# am.net
KiCad netlist of a schematic drawn in Altium Designer
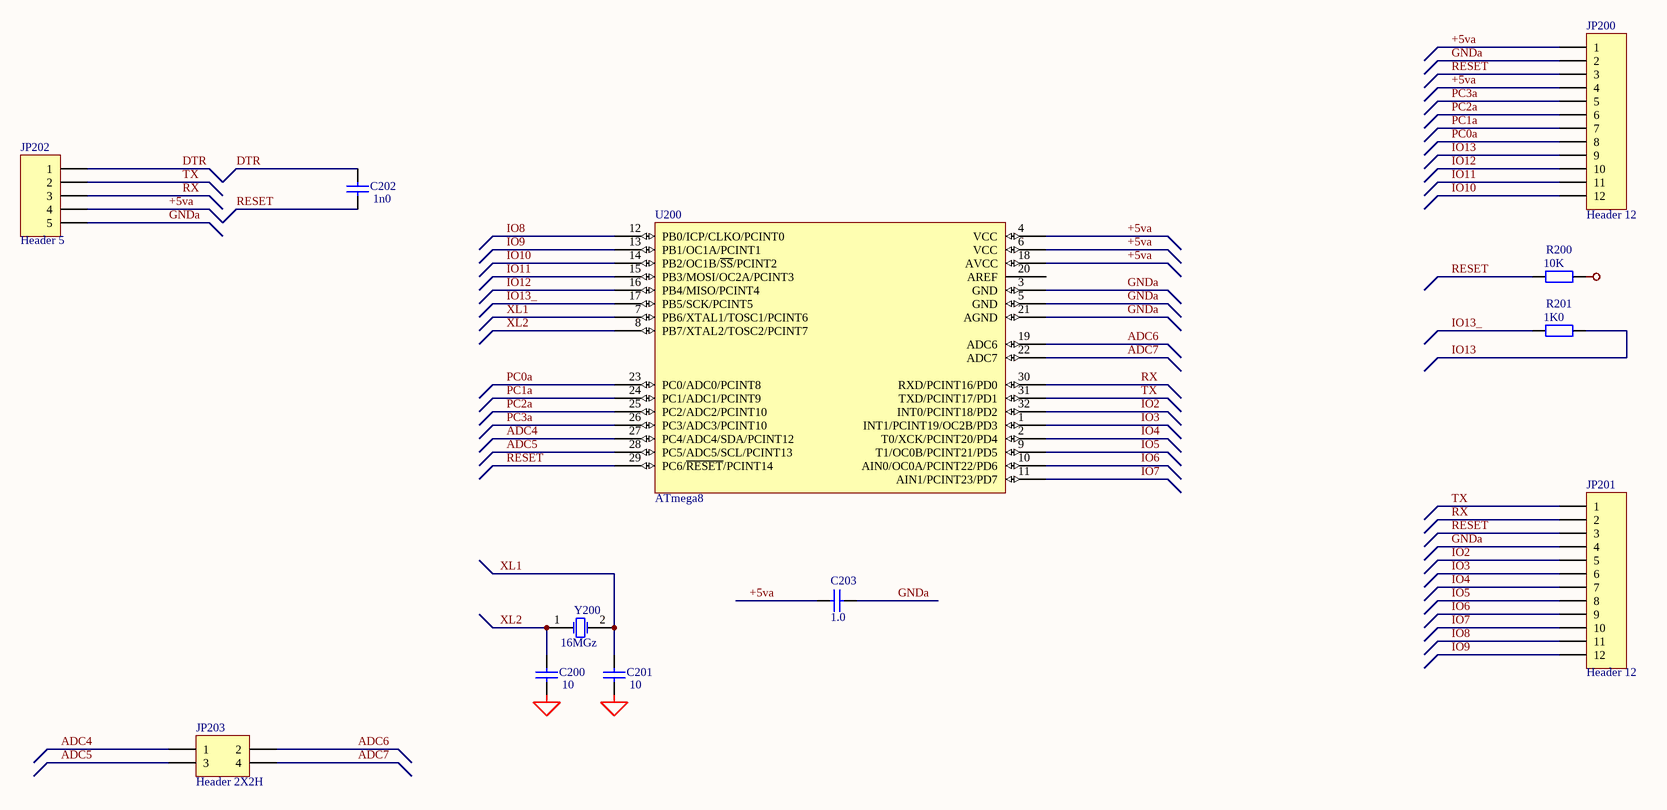
[diagram p0: am.SCHDOC]

(export (version "E")
  (design (tool "Eeschema 10.0.6"))
  (components
    (comp (ref "C200")
      (value "10")
      (footprint "_1206")
      (description "Capacitor")
      (fields (field (name "MANUFACTURER") "Generic Components") (field (name "PUBLISHER") "Altium Limited"))
      (libsource (lib "Miscellaneous Devices") (part "Cap Semi"))
    )
    (comp (ref "C201")
      (value "10")
      (footprint "_1206")
      (description "Capacitor")
      (fields (field (name "MANUFACTURER") "Generic Components") (field (name "PUBLISHER") "Altium Limited"))
      (libsource (lib "Miscellaneous Devices") (part "Cap Semi"))
    )
    (comp (ref "C202")
      (value "1n0")
      (footprint "_1206")
      (description "Capacitor")
      (fields (field (name "MANUFACTURER") "Generic Components") (field (name "PUBLISHER") "Altium Limited"))
      (libsource (lib "Miscellaneous Devices") (part "Cap Semi"))
    )
    (comp (ref "C203")
      (value "1.0")
      (footprint "_1206")
      (description "Capacitor")
      (fields (field (name "MANUFACTURER") "Generic Components") (field (name "PUBLISHER") "Altium Limited"))
      (libsource (lib "Miscellaneous Devices") (part "Cap Semi"))
    )
    (comp (ref "JP200")
      (value "Header 12")
      (footprint "HDR1X12")
      (description "Header, 12-Pin")
      (fields (field (name "MANUFACTURER") "Generic Components") (field (name "PUBLISHER") "Altium Limited"))
      (libsource (lib "Miscellaneous Connectors") (part "Header 12"))
    )
    (comp (ref "JP201")
      (value "Header 12")
      (footprint "HDR1X12")
      (description "Header, 12-Pin")
      (fields (field (name "MANUFACTURER") "Generic Components") (field (name "PUBLISHER") "Altium Limited"))
      (libsource (lib "Miscellaneous Connectors") (part "Header 12"))
    )
    (comp (ref "JP202")
      (value "Header 5")
      (footprint "HDR1X5")
      (description "Header, 5-Pin")
      (fields (field (name "MANUFACTURER") "Generic Components") (field (name "PUBLISHER") "Altium Limited"))
      (libsource (lib "Miscellaneous Connectors") (part "Header 5"))
    )
    (comp (ref "JP203")
      (value "Header 2X2H")
      (footprint "HDR2X2")
      (description "Header, 2-Pin, Dual row,  Right Angle")
      (fields (field (name "MANUFACTURER") "Generic Components") (field (name "PUBLISHER") "Altium Limited"))
      (libsource (lib "Miscellaneous Connectors") (part "Header 2X2H"))
    )
    (comp (ref "R200")
      (value "10K")
      (footprint "_1206")
      (description "Resistor")
      (fields (field (name "MANUFACTURER") "Generic Components") (field (name "PUBLISHER") "Altium Limited"))
      (libsource (lib "Miscellaneous Devices") (part "Res2"))
    )
    (comp (ref "R201")
      (value "1K0")
      (footprint "_1206")
      (description "Resistor")
      (fields (field (name "MANUFACTURER") "Generic Components") (field (name "PUBLISHER") "Altium Limited"))
      (libsource (lib "Miscellaneous Devices") (part "Res2"))
    )
    (comp (ref "U200")
      (value "ATmega8")
      (footprint "QFP7X7-G32/X.5N")
      (libsource (lib "PAL") (part "ATmega48/TQFP"))
    )
    (comp (ref "Y200")
      (value "16MGz")
      (footprint "qwarz1")
      (description "Crystal Oscillator")
      (fields (field (name "MANUFACTURER") "Generic Components") (field (name "PUBLISHER") "Altium Limited"))
      (libsource (lib "Miscellaneous Devices") (part "XTAL"))
    )
  )
  (nets
    (net (code "1") (name "+5va") (class "Default")
      (node (ref "C203") (pin "2") (pinfunction "2_2") (pintype "passive"))
      (node (ref "JP200") (pin "1") (pinfunction "1_1") (pintype "passive"))
      (node (ref "JP200") (pin "4") (pinfunction "4_4") (pintype "passive"))
      (node (ref "JP202") (pin "4") (pinfunction "4_4") (pintype "passive"))
      (node (ref "R200") (pin "1") (pinfunction "1_1") (pintype "passive"))
      (node (ref "U200") (pin "18") (pinfunction "AVCC_18") (pintype "bidirectional"))
      (node (ref "U200") (pin "4") (pinfunction "VCC_4") (pintype "bidirectional"))
      (node (ref "U200") (pin "6") (pinfunction "VCC_6") (pintype "bidirectional"))
    )
    (net (code "2") (name "/ADC4") (class "Default")
      (node (ref "JP203") (pin "1") (pinfunction "1_1") (pintype "passive"))
      (node (ref "U200") (pin "27") (pinfunction "PC4/ADC4/SDA/PCINT12_27") (pintype "bidirectional"))
    )
    (net (code "3") (name "/ADC5") (class "Default")
      (node (ref "JP203") (pin "3") (pinfunction "3_3") (pintype "passive"))
      (node (ref "U200") (pin "28") (pinfunction "PC5/ADC5/SCL/PCINT13_28") (pintype "bidirectional"))
    )
    (net (code "4") (name "/ADC6") (class "Default")
      (node (ref "JP203") (pin "2") (pinfunction "2_2") (pintype "passive"))
      (node (ref "U200") (pin "19") (pinfunction "ADC6_19") (pintype "bidirectional"))
    )
    (net (code "5") (name "/ADC7") (class "Default")
      (node (ref "JP203") (pin "4") (pinfunction "4_4") (pintype "passive"))
      (node (ref "U200") (pin "22") (pinfunction "ADC7_22") (pintype "bidirectional"))
    )
    (net (code "6") (name "/DTR") (class "Default")
      (node (ref "C202") (pin "2") (pinfunction "2_2") (pintype "passive"))
      (node (ref "JP202") (pin "1") (pinfunction "1_1") (pintype "passive"))
    )
    (net (code "7") (name "/IO2") (class "Default")
      (node (ref "JP201") (pin "5") (pinfunction "5_5") (pintype "passive"))
      (node (ref "U200") (pin "32") (pinfunction "INT0/PCINT18/PD2_32") (pintype "bidirectional"))
    )
    (net (code "8") (name "/IO3") (class "Default")
      (node (ref "JP201") (pin "6") (pinfunction "6_6") (pintype "passive"))
      (node (ref "U200") (pin "1") (pinfunction "INT1/PCINT19/OC2B/PD3_1") (pintype "bidirectional"))
    )
    (net (code "9") (name "/IO4") (class "Default")
      (node (ref "JP201") (pin "7") (pinfunction "7_7") (pintype "passive"))
      (node (ref "U200") (pin "2") (pinfunction "T0/XCK/PCINT20/PD4_2") (pintype "bidirectional"))
    )
    (net (code "10") (name "/IO5") (class "Default")
      (node (ref "JP201") (pin "8") (pinfunction "8_8") (pintype "passive"))
      (node (ref "U200") (pin "9") (pinfunction "T1/OC0B/PCINT21/PD5_9") (pintype "bidirectional"))
    )
    (net (code "11") (name "/IO6") (class "Default")
      (node (ref "JP201") (pin "9") (pinfunction "9_9") (pintype "passive"))
      (node (ref "U200") (pin "10") (pinfunction "AIN0/OC0A/PCINT22/PD6_10") (pintype "bidirectional"))
    )
    (net (code "12") (name "/IO7") (class "Default")
      (node (ref "JP201") (pin "10") (pinfunction "10_10") (pintype "passive"))
      (node (ref "U200") (pin "11") (pinfunction "AIN1/PCINT23/PD7_11") (pintype "bidirectional"))
    )
    (net (code "13") (name "/IO8") (class "Default")
      (node (ref "JP201") (pin "11") (pinfunction "11_11") (pintype "passive"))
      (node (ref "U200") (pin "12") (pinfunction "PB0/ICP/CLKO/PCINT0_12") (pintype "bidirectional"))
    )
    (net (code "14") (name "/IO9") (class "Default")
      (node (ref "JP201") (pin "12") (pinfunction "12_12") (pintype "passive"))
      (node (ref "U200") (pin "13") (pinfunction "PB1/OC1A/PCINT1_13") (pintype "bidirectional"))
    )
    (net (code "15") (name "/IO10") (class "Default")
      (node (ref "JP200") (pin "12") (pinfunction "12_12") (pintype "passive"))
      (node (ref "U200") (pin "14") (pinfunction "PB2/OC1B/~{SS}/PCINT2_14") (pintype "bidirectional"))
    )
    (net (code "16") (name "/IO11") (class "Default")
      (node (ref "JP200") (pin "11") (pinfunction "11_11") (pintype "passive"))
      (node (ref "U200") (pin "15") (pinfunction "PB3/MOSI/OC2A/PCINT3_15") (pintype "bidirectional"))
    )
    (net (code "17") (name "/IO12") (class "Default")
      (node (ref "JP200") (pin "10") (pinfunction "10_10") (pintype "passive"))
      (node (ref "U200") (pin "16") (pinfunction "PB4/MISO/PCINT4_16") (pintype "bidirectional"))
    )
    (net (code "18") (name "/IO13") (class "Default")
      (node (ref "JP200") (pin "9") (pinfunction "9_9") (pintype "passive"))
      (node (ref "R201") (pin "1") (pinfunction "1_1") (pintype "passive"))
    )
    (net (code "19") (name "/IO13_") (class "Default")
      (node (ref "R201") (pin "2") (pinfunction "2_2") (pintype "passive"))
      (node (ref "U200") (pin "17") (pinfunction "PB5/SCK/PCINT5_17") (pintype "bidirectional"))
    )
    (net (code "20") (name "/PC0a") (class "Default")
      (node (ref "JP200") (pin "8") (pinfunction "8_8") (pintype "passive"))
      (node (ref "U200") (pin "23") (pinfunction "PC0/ADC0/PCINT8_23") (pintype "bidirectional"))
    )
    (net (code "21") (name "/PC1a") (class "Default")
      (node (ref "JP200") (pin "7") (pinfunction "7_7") (pintype "passive"))
      (node (ref "U200") (pin "24") (pinfunction "PC1/ADC1/PCINT9_24") (pintype "bidirectional"))
    )
    (net (code "22") (name "/PC2a") (class "Default")
      (node (ref "JP200") (pin "6") (pinfunction "6_6") (pintype "passive"))
      (node (ref "U200") (pin "25") (pinfunction "PC2/ADC2/PCINT10_25") (pintype "bidirectional"))
    )
    (net (code "23") (name "/PC3a") (class "Default")
      (node (ref "JP200") (pin "5") (pinfunction "5_5") (pintype "passive"))
      (node (ref "U200") (pin "26") (pinfunction "PC3/ADC3/PCINT10_26") (pintype "bidirectional"))
    )
    (net (code "24") (name "/RESET") (class "Default")
      (node (ref "C202") (pin "1") (pinfunction "1_1") (pintype "passive"))
      (node (ref "JP200") (pin "3") (pinfunction "3_3") (pintype "passive"))
      (node (ref "JP201") (pin "3") (pinfunction "3_3") (pintype "passive"))
      (node (ref "R200") (pin "2") (pinfunction "2_2") (pintype "passive"))
      (node (ref "U200") (pin "29") (pinfunction "PC6/~{RESET}/PCINT14_29") (pintype "bidirectional"))
    )
    (net (code "25") (name "/RX") (class "Default")
      (node (ref "JP201") (pin "2") (pinfunction "2_2") (pintype "passive"))
      (node (ref "JP202") (pin "3") (pinfunction "3_3") (pintype "passive"))
      (node (ref "U200") (pin "30") (pinfunction "RXD/PCINT16/PD0_30") (pintype "bidirectional"))
    )
    (net (code "26") (name "/TX") (class "Default")
      (node (ref "JP201") (pin "1") (pinfunction "1_1") (pintype "passive"))
      (node (ref "JP202") (pin "2") (pinfunction "2_2") (pintype "passive"))
      (node (ref "U200") (pin "31") (pinfunction "TXD/PCINT17/PD1_31") (pintype "bidirectional"))
    )
    (net (code "27") (name "/XL1") (class "Default")
      (node (ref "C201") (pin "2") (pinfunction "2_2") (pintype "passive"))
      (node (ref "U200") (pin "7") (pinfunction "PB6/XTAL1/TOSC1/PCINT6_7") (pintype "bidirectional"))
      (node (ref "Y200") (pin "2") (pinfunction "OSC2_2") (pintype "passive"))
    )
    (net (code "28") (name "/XL2") (class "Default")
      (node (ref "C200") (pin "2") (pinfunction "2_2") (pintype "passive"))
      (node (ref "U200") (pin "8") (pinfunction "PB7/XTAL2/TOSC2/PCINT7_8") (pintype "bidirectional"))
      (node (ref "Y200") (pin "1") (pinfunction "OSC1_1") (pintype "passive"))
    )
    (net (code "29") (name "GNDa") (class "Default")
      (node (ref "C200") (pin "1") (pinfunction "1_1") (pintype "passive"))
      (node (ref "C201") (pin "1") (pinfunction "1_1") (pintype "passive"))
      (node (ref "C203") (pin "1") (pinfunction "1_1") (pintype "passive"))
      (node (ref "JP200") (pin "2") (pinfunction "2_2") (pintype "passive"))
      (node (ref "JP201") (pin "4") (pinfunction "4_4") (pintype "passive"))
      (node (ref "JP202") (pin "5") (pinfunction "5_5") (pintype "passive"))
      (node (ref "U200") (pin "21") (pinfunction "AGND_21") (pintype "bidirectional"))
      (node (ref "U200") (pin "3") (pinfunction "GND_3") (pintype "bidirectional"))
      (node (ref "U200") (pin "5") (pinfunction "GND_5") (pintype "bidirectional"))
    )
    (net (code "30") (name "unconnected-(U200-AREF-Pad20)") (class "Default")
      (node (ref "U200") (pin "20") (pinfunction "AREF_20") (pintype "passive"))
    )
  )
)
